# ESIMA_E-Meter_CPUBlock.net
KiCad netlist of a schematic drawn in Altium Designer
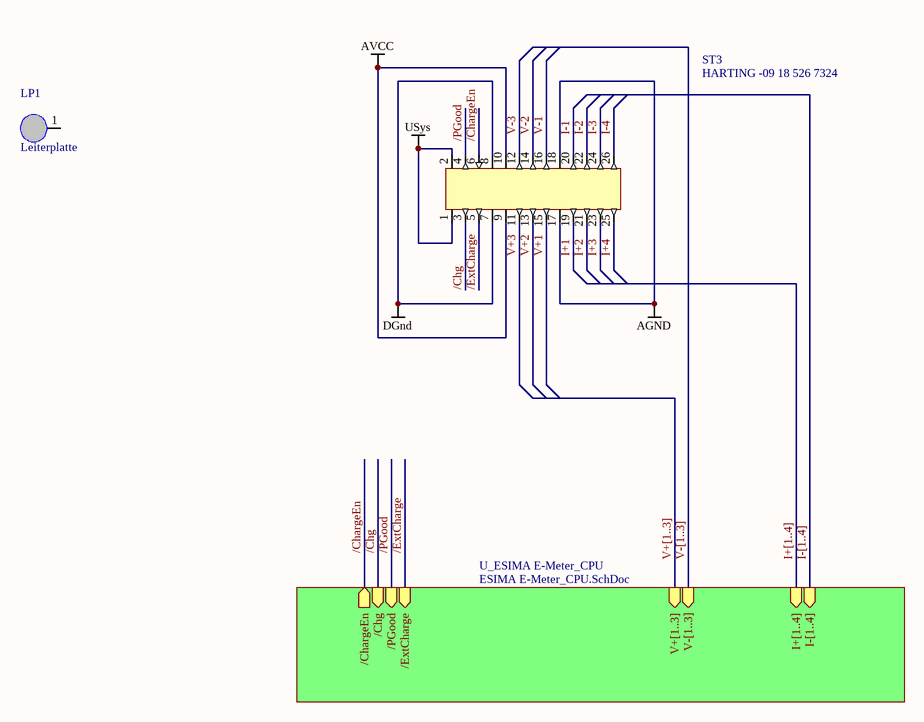
[diagram p0: ESIMA E-Meter_CPUBlock.SchDoc]

(export (version "E")
  (design (tool "Eeschema 10.0.6"))
  (components
    (comp (ref "LP1")
      (value "Leiterplatte")
      (description "Platzhalter für Leiterplatte PCB-Pool in Stückliste")
      (libsource (lib "JM_Elektromechanik") (part "Passmarke 1mm"))
    )
    (comp (ref "ST3")
      (value "HARTING -09 18 526 7324")
      (footprint "HARTING -09 18 526 7324")
      (libsource (lib "JM_Elektromechanik") (part "Stecker 26Pol zweireihig universal"))
    )
  )
  (nets
    (net (code "1") (name "/I+1") (class "Default")
      (node (ref "ST3") (pin "19") (pinfunction "19_19") (pintype "output"))
    )
    (net (code "2") (name "/I+2") (class "Default")
      (node (ref "ST3") (pin "21") (pinfunction "21_21") (pintype "output"))
    )
    (net (code "3") (name "/I+3") (class "Default")
      (node (ref "ST3") (pin "23") (pinfunction "23_23") (pintype "output"))
    )
    (net (code "4") (name "/I+4") (class "Default")
      (node (ref "ST3") (pin "25") (pinfunction "25_25") (pintype "output"))
    )
    (net (code "6") (name "/I-1") (class "Default")
      (node (ref "ST3") (pin "20") (pinfunction "20_20") (pintype "output"))
    )
    (net (code "7") (name "/I-2") (class "Default")
      (node (ref "ST3") (pin "22") (pinfunction "22_22") (pintype "output"))
    )
    (net (code "8") (name "/I-3") (class "Default")
      (node (ref "ST3") (pin "24") (pinfunction "24_24") (pintype "output"))
    )
    (net (code "9") (name "/I-4") (class "Default")
      (node (ref "ST3") (pin "26") (pinfunction "26_26") (pintype "output"))
    )
    (net (code "11") (name "/V+1") (class "Default")
      (node (ref "ST3") (pin "15") (pinfunction "15_15") (pintype "output"))
    )
    (net (code "12") (name "/V+2") (class "Default")
      (node (ref "ST3") (pin "13") (pinfunction "13_13") (pintype "output"))
    )
    (net (code "13") (name "/V+3") (class "Default")
      (node (ref "ST3") (pin "11") (pinfunction "11_11") (pintype "output"))
    )
    (net (code "15") (name "/V-1") (class "Default")
      (node (ref "ST3") (pin "16") (pinfunction "16_16") (pintype "output"))
    )
    (net (code "16") (name "/V-2") (class "Default")
      (node (ref "ST3") (pin "14") (pinfunction "14_14") (pintype "output"))
    )
    (net (code "17") (name "/V-3") (class "Default")
      (node (ref "ST3") (pin "12") (pinfunction "12_12") (pintype "output"))
    )
    (net (code "19") (name "/{slash}ChargeEn") (class "Default")
      (node (ref "ST3") (pin "6") (pinfunction "6_6") (pintype "input"))
    )
    (net (code "20") (name "/{slash}Chg") (class "Default")
      (node (ref "ST3") (pin "3") (pinfunction "3_3") (pintype "output"))
    )
    (net (code "21") (name "/{slash}ExtCharge") (class "Default")
      (node (ref "ST3") (pin "5") (pinfunction "5_5") (pintype "output"))
    )
    (net (code "22") (name "/{slash}PGood") (class "Default")
      (node (ref "ST3") (pin "4") (pinfunction "4_4") (pintype "output"))
    )
    (net (code "23") (name "AGND") (class "Default")
      (node (ref "ST3") (pin "17") (pinfunction "17_17") (pintype "passive"))
      (node (ref "ST3") (pin "18") (pinfunction "18_18") (pintype "passive"))
    )
    (net (code "24") (name "AVCC") (class "Default")
      (node (ref "ST3") (pin "10") (pinfunction "10_10") (pintype "passive"))
      (node (ref "ST3") (pin "9") (pinfunction "9_9") (pintype "passive"))
    )
    (net (code "25") (name "DGnd") (class "Default")
      (node (ref "ST3") (pin "7") (pinfunction "7_7") (pintype "passive"))
      (node (ref "ST3") (pin "8") (pinfunction "8_8") (pintype "passive"))
    )
    (net (code "26") (name "USys") (class "Default")
      (node (ref "ST3") (pin "1") (pinfunction "1_1") (pintype "power_in"))
      (node (ref "ST3") (pin "2") (pinfunction "2_2") (pintype "power_in"))
    )
    (net (code "27") (name "unconnected-(LP1-Pad1)") (class "Default")
      (node (ref "LP1") (pin "1") (pinfunction "1_1") (pintype "passive"))
    )
  )
)
